# Sheet2.net
KiCad netlist of a schematic drawn in Altium Designer
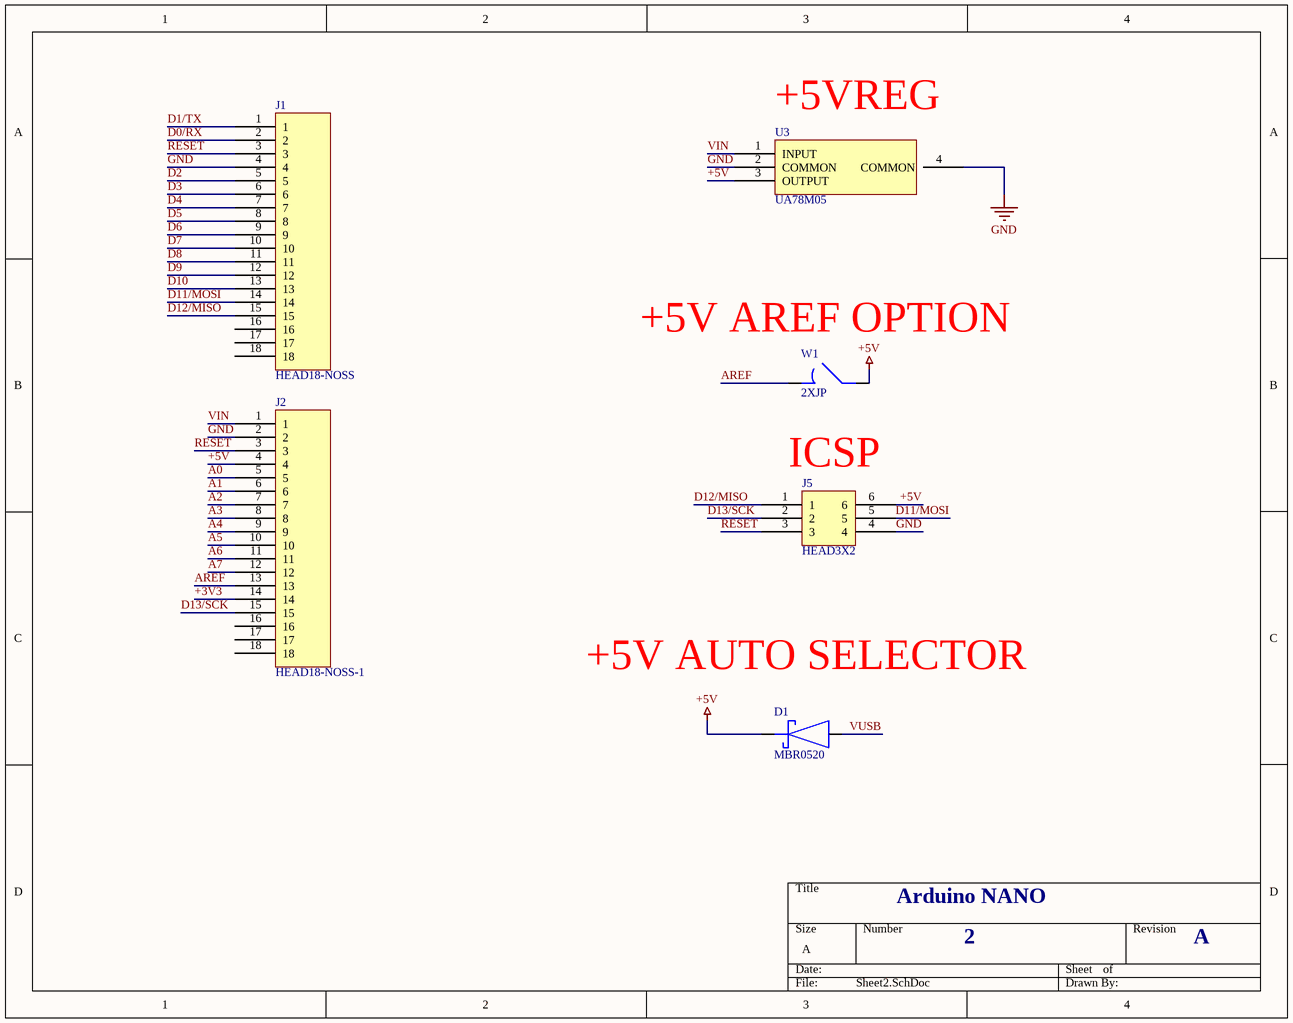
[diagram p0: Sheet2.SchDoc]

(export (version "E")
  (design (tool "Eeschema 10.0.6"))
  (components
    (comp (ref "D1")
      (value "MBR0520")
      (footprint "Diode")
      (description "DIODE SCHOTTKY 20V 0.5A SOD962")
      (fields
        (field (name "MANUFACTURER") "Nexperia")
        (field (name "MANUFACTURER PART NUMBER") "PMEG2005AESFYL")
      )
      (libsource (lib "Schlib1") (part "PMEG2005AESFYL"))
    )
    (comp (ref "J1")
      (value "HEAD18-NOSS")
      (footprint "DIP18")
      (description "Pin Strip Header, 951 Series, 9511408622AR ¦ 3M 951140-8622-AR")
      (fields (field (name "MANUFACTURER") "3M") (field (name "MANUFACTURER PART NUMBER") "951140-8622-AR"))
      (libsource (lib "Schlib1") (part "951140-8622-AR"))
    )
    (comp (ref "J2")
      (value "HEAD18-NOSS-1")
      (footprint "DIP18")
      (description "Pin Strip Header, 951 Series, 9511408622AR ¦ 3M 951140-8622-AR")
      (fields (field (name "MANUFACTURER") "3M") (field (name "MANUFACTURER PART NUMBER") "951140-8622-AR"))
      (libsource (lib "Schlib1") (part "951140-8622-AR"))
    )
    (comp (ref "J5")
      (value "HEAD3X2")
      (footprint "DIP6")
      (description "80000908477  929836-09-03-RK=6/.100/STR/HDR/2R/.23")
      (fields (field (name "MANUFACTURER") "3M") (field (name "MANUFACTURER PART NUMBER") "929836-09-03-RK"))
      (libsource (lib "Schlib1") (part "929836-09-03-RK"))
    )
    (comp (ref "U3")
      (value "UA78M05")
      (footprint "SOT223-4")
      (description "500-mA, 30-V, linear voltage regulator 4-SOT-223 0 to 125")
      (fields
        (field (name "MANUFACTURER") "Texas Instruments")
        (field (name "MANUFACTURER PART NUMBER") "UA78M05CDCYRG3")
      )
      (libsource (lib "Schlib1") (part "UA78M05CDCYRG3"))
    )
    (comp (ref "W1")
      (value "2XJP")
      (footprint "PUSH BUTTON")
      (description "Switch Tactile N.O. SPST Round Button Gull Wing 0.05A 12VDC 1.5N SMD Embossed T/R")
      (fields (field (name "MANUFACTURER") "Omron") (field (name "MANUFACTURER PART NUMBER") "B3U-1000P"))
      (libsource (lib "Schlib1") (part "B3U-1000P"))
    )
  )
  (nets
    (net (code "1") (name "+5V") (class "Default")
      (node (ref "D1") (pin "1") (pinfunction "1_1") (pintype "passive"))
      (node (ref "J2") (pin "4") (pinfunction "4_4") (pintype "passive"))
      (node (ref "J5") (pin "6") (pinfunction "6_6") (pintype "passive"))
      (node (ref "U3") (pin "3") (pinfunction "OUTPUT_3") (pintype "passive"))
      (node (ref "W1") (pin "2") (pinfunction "2_2") (pintype "passive"))
    )
    (net (code "2") (name "/+3V3") (class "Default")
      (node (ref "J2") (pin "14") (pinfunction "14_14") (pintype "passive"))
    )
    (net (code "3") (name "/A0") (class "Default")
      (node (ref "J2") (pin "5") (pinfunction "5_5") (pintype "passive"))
    )
    (net (code "4") (name "/A1") (class "Default")
      (node (ref "J2") (pin "6") (pinfunction "6_6") (pintype "passive"))
    )
    (net (code "5") (name "/A2") (class "Default")
      (node (ref "J2") (pin "7") (pinfunction "7_7") (pintype "passive"))
    )
    (net (code "6") (name "/A3") (class "Default")
      (node (ref "J2") (pin "8") (pinfunction "8_8") (pintype "passive"))
    )
    (net (code "7") (name "/A4") (class "Default")
      (node (ref "J2") (pin "9") (pinfunction "9_9") (pintype "passive"))
    )
    (net (code "8") (name "/A5") (class "Default")
      (node (ref "J2") (pin "10") (pinfunction "10_10") (pintype "passive"))
    )
    (net (code "9") (name "/A6") (class "Default")
      (node (ref "J2") (pin "11") (pinfunction "11_11") (pintype "passive"))
    )
    (net (code "10") (name "/A7") (class "Default")
      (node (ref "J2") (pin "12") (pinfunction "12_12") (pintype "passive"))
    )
    (net (code "11") (name "/AREF") (class "Default")
      (node (ref "J2") (pin "13") (pinfunction "13_13") (pintype "passive"))
      (node (ref "W1") (pin "1") (pinfunction "1_1") (pintype "passive"))
    )
    (net (code "12") (name "/D0{slash}RX") (class "Default")
      (node (ref "J1") (pin "2") (pinfunction "2_2") (pintype "passive"))
    )
    (net (code "13") (name "/D1{slash}TX") (class "Default")
      (node (ref "J1") (pin "1") (pinfunction "1_1") (pintype "passive"))
    )
    (net (code "14") (name "/D2") (class "Default")
      (node (ref "J1") (pin "5") (pinfunction "5_5") (pintype "passive"))
    )
    (net (code "15") (name "/D3") (class "Default")
      (node (ref "J1") (pin "6") (pinfunction "6_6") (pintype "passive"))
    )
    (net (code "16") (name "/D4") (class "Default")
      (node (ref "J1") (pin "7") (pinfunction "7_7") (pintype "passive"))
    )
    (net (code "17") (name "/D5") (class "Default")
      (node (ref "J1") (pin "8") (pinfunction "8_8") (pintype "passive"))
    )
    (net (code "18") (name "/D6") (class "Default")
      (node (ref "J1") (pin "9") (pinfunction "9_9") (pintype "passive"))
    )
    (net (code "19") (name "/D7") (class "Default")
      (node (ref "J1") (pin "10") (pinfunction "10_10") (pintype "passive"))
    )
    (net (code "20") (name "/D8") (class "Default")
      (node (ref "J1") (pin "11") (pinfunction "11_11") (pintype "passive"))
    )
    (net (code "21") (name "/D9") (class "Default")
      (node (ref "J1") (pin "12") (pinfunction "12_12") (pintype "passive"))
    )
    (net (code "22") (name "/D10") (class "Default")
      (node (ref "J1") (pin "13") (pinfunction "13_13") (pintype "passive"))
    )
    (net (code "23") (name "/D11{slash}MOSI") (class "Default")
      (node (ref "J1") (pin "14") (pinfunction "14_14") (pintype "passive"))
      (node (ref "J5") (pin "5") (pinfunction "5_5") (pintype "passive"))
    )
    (net (code "24") (name "/D12{slash}MISO") (class "Default")
      (node (ref "J1") (pin "15") (pinfunction "15_15") (pintype "passive"))
      (node (ref "J5") (pin "1") (pinfunction "1_1") (pintype "passive"))
    )
    (net (code "25") (name "/D13{slash}SCK") (class "Default")
      (node (ref "J2") (pin "15") (pinfunction "15_15") (pintype "passive"))
      (node (ref "J5") (pin "2") (pinfunction "2_2") (pintype "passive"))
    )
    (net (code "26") (name "/RESET") (class "Default")
      (node (ref "J1") (pin "3") (pinfunction "3_3") (pintype "passive"))
      (node (ref "J2") (pin "3") (pinfunction "3_3") (pintype "passive"))
      (node (ref "J5") (pin "3") (pinfunction "3_3") (pintype "passive"))
    )
    (net (code "27") (name "/VIN") (class "Default")
      (node (ref "J2") (pin "1") (pinfunction "1_1") (pintype "passive"))
      (node (ref "U3") (pin "1") (pinfunction "INPUT_1") (pintype "passive"))
    )
    (net (code "28") (name "/VUSB") (class "Default")
      (node (ref "D1") (pin "2") (pinfunction "2_2") (pintype "passive"))
    )
    (net (code "29") (name "GND") (class "Default")
      (node (ref "J1") (pin "4") (pinfunction "4_4") (pintype "passive"))
      (node (ref "J2") (pin "2") (pinfunction "2_2") (pintype "passive"))
      (node (ref "J5") (pin "4") (pinfunction "4_4") (pintype "passive"))
      (node (ref "U3") (pin "2") (pinfunction "COMMON_2") (pintype "passive"))
      (node (ref "U3") (pin "4") (pinfunction "COMMON_4") (pintype "passive"))
    )
    (net (code "30") (name "unconnected-(J1-Pad16)") (class "Default")
      (node (ref "J1") (pin "16") (pinfunction "16_16") (pintype "passive"))
    )
    (net (code "31") (name "unconnected-(J1-Pad17)") (class "Default")
      (node (ref "J1") (pin "17") (pinfunction "17_17") (pintype "passive"))
    )
    (net (code "32") (name "unconnected-(J1-Pad18)") (class "Default")
      (node (ref "J1") (pin "18") (pinfunction "18_18") (pintype "passive"))
    )
    (net (code "33") (name "unconnected-(J2-Pad16)") (class "Default")
      (node (ref "J2") (pin "16") (pinfunction "16_16") (pintype "passive"))
    )
    (net (code "34") (name "unconnected-(J2-Pad17)") (class "Default")
      (node (ref "J2") (pin "17") (pinfunction "17_17") (pintype "passive"))
    )
    (net (code "35") (name "unconnected-(J2-Pad18)") (class "Default")
      (node (ref "J2") (pin "18") (pinfunction "18_18") (pintype "passive"))
    )
  )
)
